# 2_1.net
KiCad netlist of a schematic drawn in Altium Designer
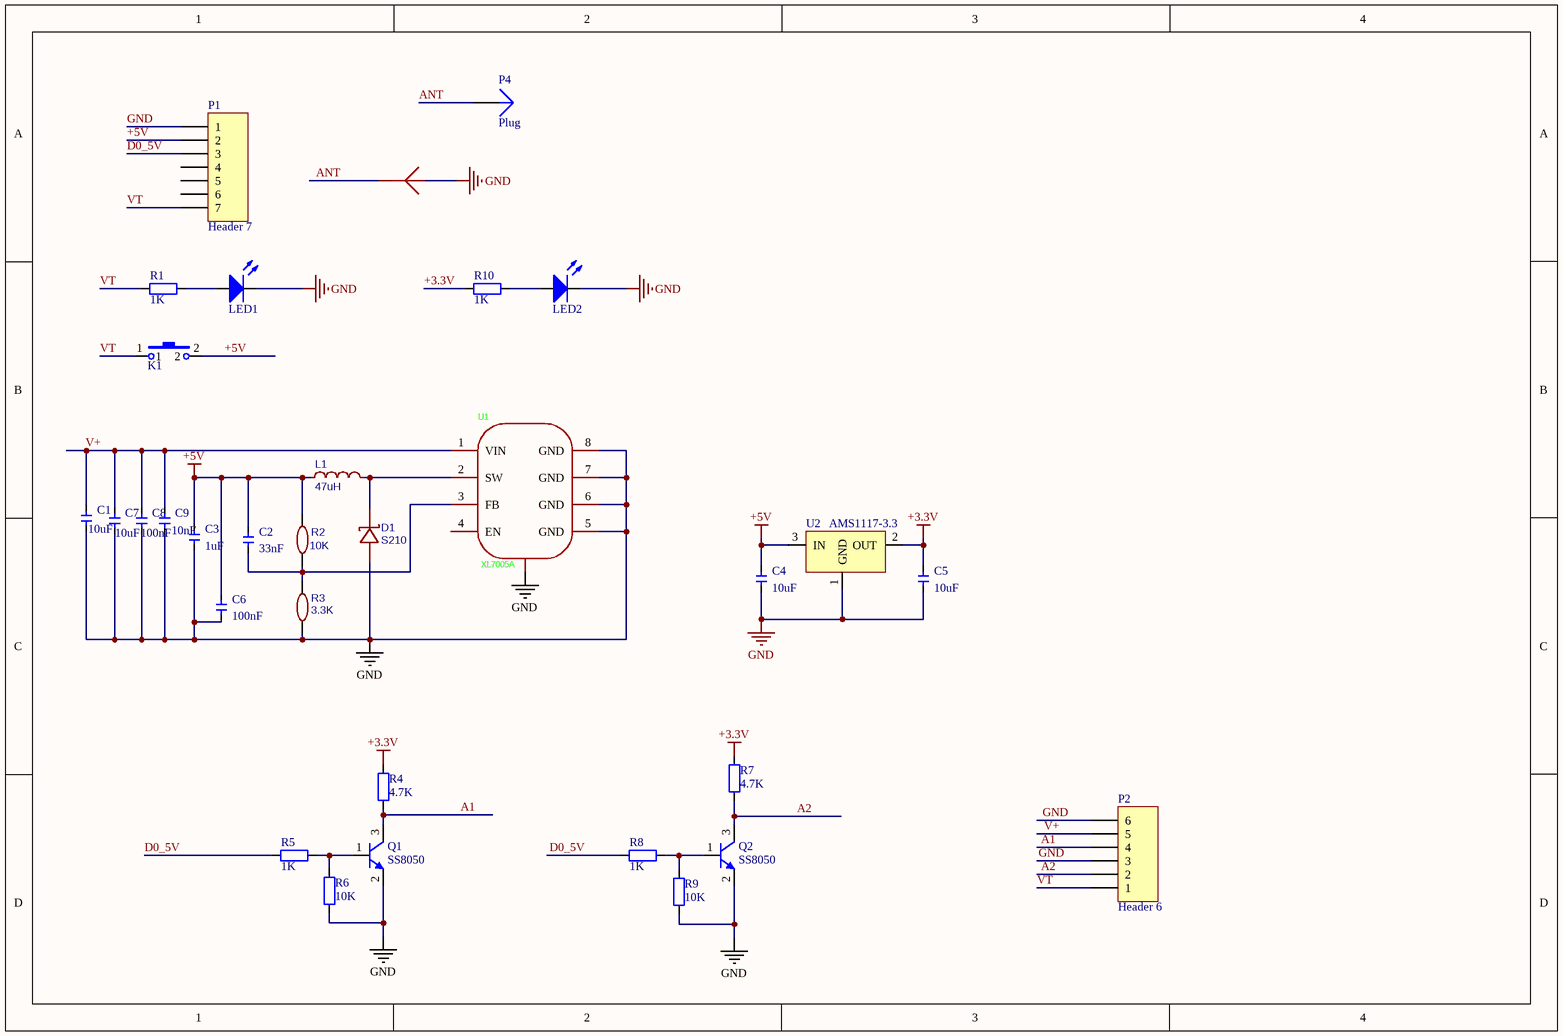
[diagram p0: 遥控2.1.SchDoc]

(export (version "E")
  (design (tool "Eeschema 10.0.6"))
  (components
    (comp (ref "C1")
      (value "10uF")
      (footprint "0805")
      (description "无极性电容")
      (fields (field (name "PUBLISHER") "Altium Limited"))
      (libsource (lib "Arrowy_Racing") (part "Cap"))
    )
    (comp (ref "C2")
      (value "33nF")
      (footprint "CAP-0603")
      (description "无极性电容")
      (fields (field (name "PUBLISHER") "Altium Limited"))
      (libsource (lib "Arrowy_Racing") (part "Cap"))
    )
    (comp (ref "C3")
      (value "1uF")
      (footprint "CAP-0603")
      (description "无极性电容")
      (fields (field (name "PUBLISHER") "Altium Limited"))
      (libsource (lib "Arrowy_Racing") (part "Cap"))
    )
    (comp (ref "C4")
      (value "10uF")
      (footprint "CAP-0603")
      (description "无极性电容")
      (fields (field (name "PUBLISHER") "Altium Limited"))
      (libsource (lib "Arrowy_Racing") (part "Cap"))
    )
    (comp (ref "C5")
      (value "10uF")
      (footprint "CAP-0603")
      (description "无极性电容")
      (fields (field (name "PUBLISHER") "Altium Limited"))
      (libsource (lib "Arrowy_Racing") (part "Cap"))
    )
    (comp (ref "C6")
      (value "100nF")
      (footprint "CAP-0603")
      (description "无极性电容")
      (fields (field (name "PUBLISHER") "Altium Limited"))
      (libsource (lib "Arrowy_Racing") (part "Cap"))
    )
    (comp (ref "C7")
      (value "10uF")
      (footprint "0805")
      (description "无极性电容")
      (fields (field (name "PUBLISHER") "Altium Limited"))
      (libsource (lib "Arrowy_Racing") (part "Cap"))
    )
    (comp (ref "C8")
      (value "100nF")
      (footprint "0805")
      (description "无极性电容")
      (fields (field (name "PUBLISHER") "Altium Limited"))
      (libsource (lib "Arrowy_Racing") (part "Cap"))
    )
    (comp (ref "C9")
      (value "10nF")
      (footprint "0805")
      (description "无极性电容")
      (fields (field (name "PUBLISHER") "Altium Limited"))
      (libsource (lib "Arrowy_Racing") (part "Cap"))
    )
    (comp (ref "D1")
      (value "S210")
      (footprint "SOD-123")
      (fields (field (name "MANUFACTURER PART") "B340A") (field (name "MANUFACTURER") "MDD"))
      (libsource (lib "altium-import") (part "root_3_B340A_"))
    )
    (comp (ref "K1")
      (value "SW-PB")
      (footprint "SW-SMD_L3.9-W3.0-P4.45")
      (description "微动开关")
      (fields (field (name "SUPPLITER PART") "C961737") (field (name "PUBLISHER") "Altium Limited"))
      (libsource (lib "Arrowy_Racing") (part "SW-PB"))
    )
    (comp (ref "L1")
      (value "47uH")
      (footprint "IND-SMD_L4.0-W4.0_FNR4012S")
      (fields (field (name "MANUFACTURER") "SXN") (field (name "MANUFACTURER PART") "SMDRI127-680MT"))
      (libsource (lib "altium-import") (part "root_0_68uH_"))
    )
    (comp (ref "L2")
      (value "400-1000mhz-chip(b&t-1503)")
      (footprint "ANT-SMD_L15.0-W3.0")
      (description "天线类型:贴片天线;中心频率:700MHz;带宽:600MHz;增益:2dBi;功率:4W;驻波比:2;")
      (fields
        (field (name "MANUFACTURER") "Ai-Thinker(安信可)")
        (field (name "MANUFACTURERPART") "400-1000MHz-chip(B&T-1503)")
      )
      (libsource (lib "altium-import") (part "root_3_400-1000mhz-chip(b&t-1503)_"))
    )
    (comp (ref "LED1")
      (value "LED")
      (footprint "LED_0805")
      (description "发光二极管")
      (fields (field (name "PUBLISHER") "Altium Limited"))
      (libsource (lib "Arrowy_Racing") (part "LED"))
    )
    (comp (ref "LED2")
      (value "LED")
      (footprint "LED_0805")
      (description "发光二极管")
      (fields (field (name "PUBLISHER") "Altium Limited"))
      (libsource (lib "Arrowy_Racing") (part "LED"))
    )
    (comp (ref "P1")
      (value "Header 7")
      (footprint "HDR1X7")
      (description "Header, 7-Pin")
      (fields (field (name "PUBLISHER") "Altium Limited"))
      (libsource (lib "Miscellaneous Connectors") (part "Header 7"))
    )
    (comp (ref "P2")
      (value "Header 6")
      (footprint "HDR1X6")
      (description "Header, 6-Pin")
      (fields (field (name "PUBLISHER") "Altium Limited"))
      (libsource (lib "Miscellaneous Connectors") (part "Header 6"))
    )
    (comp (ref "P4")
      (value "Plug")
      (footprint "HEADER_1")
      (description "安装孔")
      (fields (field (name "PUBLISHER") "Altium Limited"))
      (libsource (lib "Arrowy_Racing") (part "Plug"))
    )
    (comp (ref "Q1")
      (value "SS8050")
      (footprint "SOT-23")
      (description "NPN贴片三极管")
      (fields (field (name "PUBLISHER") "Altium Limited"))
      (libsource (lib "Arrowy_Racing") (part "SS8050"))
    )
    (comp (ref "Q2")
      (value "SS8050")
      (footprint "SOT-23")
      (description "NPN贴片三极管")
      (fields (field (name "PUBLISHER") "Altium Limited"))
      (libsource (lib "Arrowy_Racing") (part "SS8050"))
    )
    (comp (ref "R1")
      (value "1K")
      (footprint "0603 - duplicate1")
      (description "贴片电阻")
      (fields (field (name "PUBLISHER") "Altium Limited"))
      (libsource (lib "") (part "Res_1"))
    )
    (comp (ref "R2")
      (value "10K")
      (footprint "0603 - duplicate1")
      (fields (field (name "MANUFACTURER") "UniOhm") (field (name "MANUFACTURER PART") "0603WAF1001T5E"))
      (libsource (lib "altium-import") (part "root_1_1K_"))
    )
    (comp (ref "R3")
      (value "3.3K")
      (footprint "0603 - duplicate1")
      (fields (field (name "MANUFACTURER") "UniOhm") (field (name "MANUFACTURER PART") "0603WAF3001T5E"))
      (libsource (lib "altium-import") (part "root_3_3K_"))
    )
    (comp (ref "R4")
      (value "4.7K")
      (footprint "0603 - duplicate1")
      (description "贴片电阻")
      (fields (field (name "PUBLISHER") "Altium Limited"))
      (libsource (lib "") (part "Res_3"))
    )
    (comp (ref "R5")
      (value "1K")
      (footprint "0603 - duplicate1")
      (description "贴片电阻")
      (fields (field (name "PUBLISHER") "Altium Limited"))
      (libsource (lib "") (part "Res_2"))
    )
    (comp (ref "R6")
      (value "10K")
      (footprint "0603 - duplicate1")
      (description "贴片电阻")
      (fields (field (name "PUBLISHER") "Altium Limited"))
      (libsource (lib "Arrowy_Racing") (part "Res"))
    )
    (comp (ref "R7")
      (value "4.7K")
      (footprint "0603 - duplicate1")
      (description "贴片电阻")
      (fields (field (name "PUBLISHER") "Altium Limited"))
      (libsource (lib "") (part "Res_3"))
    )
    (comp (ref "R8")
      (value "1K")
      (footprint "0603 - duplicate1")
      (description "贴片电阻")
      (fields (field (name "PUBLISHER") "Altium Limited"))
      (libsource (lib "") (part "Res_2"))
    )
    (comp (ref "R9")
      (value "10K")
      (footprint "0603 - duplicate1")
      (description "贴片电阻")
      (fields (field (name "PUBLISHER") "Altium Limited"))
      (libsource (lib "Arrowy_Racing") (part "Res"))
    )
    (comp (ref "R10")
      (value "1K")
      (footprint "0603 - duplicate1")
      (description "贴片电阻")
      (fields (field (name "PUBLISHER") "Altium Limited"))
      (libsource (lib "") (part "Res_1"))
    )
    (comp (ref "U1")
      (value "XL7005A")
      (footprint "SOIC-8_L4.9-W3.9-P1.27-LS6.0-BL-EP3.1-1")
      (fields (field (name "MANUFACTURER") "XLSEMI(芯龙)"))
      (libsource (lib "altium-import") (part "root_0_XL7005A_"))
    )
    (comp (ref "U2")
      (value "AMS1117-3.3")
      (footprint "SOT89")
      (description "3.3V稳压芯片")
      (libsource (lib "Arrowy_Racing") (part "AMS1117"))
    )
  )
  (nets
    (net (code "1") (name "+3.3V") (class "Default")
      (node (ref "C5") (pin "2") (pinfunction "2_2") (pintype "passive"))
      (node (ref "R10") (pin "2") (pinfunction "2_2") (pintype "passive"))
      (node (ref "R4") (pin "1") (pinfunction "1_1") (pintype "passive"))
      (node (ref "R7") (pin "1") (pinfunction "1_1") (pintype "passive"))
      (node (ref "U2") (pin "2") (pinfunction "OUT_2") (pintype "passive"))
    )
    (net (code "2") (name "+5V") (class "Default")
      (node (ref "C2") (pin "2") (pinfunction "2_2") (pintype "passive"))
      (node (ref "C3") (pin "2") (pinfunction "2_2") (pintype "passive"))
      (node (ref "C4") (pin "2") (pinfunction "2_2") (pintype "passive"))
      (node (ref "C6") (pin "2") (pinfunction "2_2") (pintype "passive"))
      (node (ref "K1") (pin "2") (pinfunction "2_2") (pintype "passive"))
      (node (ref "L1") (pin "1") (pinfunction "1_1") (pintype "passive"))
      (node (ref "P1") (pin "2") (pinfunction "2_2") (pintype "passive"))
      (node (ref "R2") (pin "2") (pinfunction "2_2") (pintype "passive"))
      (node (ref "U2") (pin "3") (pinfunction "IN_3") (pintype "passive"))
    )
    (net (code "3") (name "/A1") (class "Default")
      (node (ref "P2") (pin "4") (pinfunction "4_4") (pintype "passive"))
      (node (ref "Q1") (pin "3") (pinfunction "C_3") (pintype "passive"))
      (node (ref "R4") (pin "2") (pinfunction "2_2") (pintype "passive"))
    )
    (net (code "4") (name "/A2") (class "Default")
      (node (ref "P2") (pin "2") (pinfunction "2_2") (pintype "passive"))
      (node (ref "Q2") (pin "3") (pinfunction "C_3") (pintype "passive"))
      (node (ref "R7") (pin "2") (pinfunction "2_2") (pintype "passive"))
    )
    (net (code "5") (name "/ANT") (class "Default")
      (node (ref "L2") (pin "1") (pinfunction "ANT_1") (pintype "passive"))
      (node (ref "P4") (pin "1") (pinfunction "1_1") (pintype "passive"))
    )
    (net (code "6") (name "/D0_5V") (class "Default")
      (node (ref "P1") (pin "3") (pinfunction "3_3") (pintype "passive"))
      (node (ref "R5") (pin "1") (pinfunction "1_1") (pintype "passive"))
      (node (ref "R8") (pin "1") (pinfunction "1_1") (pintype "passive"))
    )
    (net (code "7") (name "/V+") (class "Default")
      (node (ref "C1") (pin "2") (pinfunction "2_2") (pintype "passive"))
      (node (ref "C7") (pin "2") (pinfunction "2_2") (pintype "passive"))
      (node (ref "C8") (pin "2") (pinfunction "2_2") (pintype "passive"))
      (node (ref "C9") (pin "2") (pinfunction "2_2") (pintype "passive"))
      (node (ref "P2") (pin "5") (pinfunction "5_5") (pintype "passive"))
      (node (ref "U1") (pin "1") (pinfunction "VIN_1") (pintype "passive"))
    )
    (net (code "8") (name "/VT") (class "Default")
      (node (ref "K1") (pin "1") (pinfunction "1_1") (pintype "passive"))
      (node (ref "P1") (pin "7") (pinfunction "7_7") (pintype "passive"))
      (node (ref "P2") (pin "1") (pinfunction "1_1") (pintype "passive"))
      (node (ref "R1") (pin "2") (pinfunction "2_2") (pintype "passive"))
    )
    (net (code "9") (name "GND") (class "Default")
      (node (ref "C1") (pin "1") (pinfunction "1_1") (pintype "passive"))
      (node (ref "C3") (pin "1") (pinfunction "1_1") (pintype "passive"))
      (node (ref "C4") (pin "1") (pinfunction "1_1") (pintype "passive"))
      (node (ref "C5") (pin "1") (pinfunction "1_1") (pintype "passive"))
      (node (ref "C6") (pin "1") (pinfunction "1_1") (pintype "passive"))
      (node (ref "C7") (pin "1") (pinfunction "1_1") (pintype "passive"))
      (node (ref "C8") (pin "1") (pinfunction "1_1") (pintype "passive"))
      (node (ref "C9") (pin "1") (pinfunction "1_1") (pintype "passive"))
      (node (ref "D1") (pin "2") (pinfunction "A_2") (pintype "passive"))
      (node (ref "L2") (pin "2") (pinfunction "2_2") (pintype "passive"))
      (node (ref "LED1") (pin "2") (pinfunction "K_2") (pintype "passive"))
      (node (ref "LED2") (pin "2") (pinfunction "K_2") (pintype "passive"))
      (node (ref "P1") (pin "1") (pinfunction "1_1") (pintype "passive"))
      (node (ref "P2") (pin "3") (pinfunction "3_3") (pintype "passive"))
      (node (ref "P2") (pin "6") (pinfunction "6_6") (pintype "passive"))
      (node (ref "Q1") (pin "2") (pinfunction "E_2") (pintype "passive"))
      (node (ref "Q2") (pin "2") (pinfunction "E_2") (pintype "passive"))
      (node (ref "R3") (pin "2") (pinfunction "2_2") (pintype "passive"))
      (node (ref "R6") (pin "1") (pinfunction "1_1") (pintype "passive"))
      (node (ref "R9") (pin "1") (pinfunction "1_1") (pintype "passive"))
      (node (ref "U1") (pin "5") (pinfunction "GND_5") (pintype "passive"))
      (node (ref "U1") (pin "6") (pinfunction "GND_6") (pintype "passive"))
      (node (ref "U1") (pin "7") (pinfunction "GND_7") (pintype "passive"))
      (node (ref "U1") (pin "8") (pinfunction "GND_8") (pintype "passive"))
      (node (ref "U1") (pin "9") (pinfunction "9_9") (pintype "passive"))
      (node (ref "U2") (pin "1") (pinfunction "GND_1") (pintype "passive"))
    )
    (net (code "10") (name "Net-(D1-K)") (class "Default")
      (node (ref "D1") (pin "1") (pinfunction "K_1") (pintype "passive"))
      (node (ref "L1") (pin "2") (pinfunction "2_2") (pintype "passive"))
      (node (ref "U1") (pin "2") (pinfunction "SW_2") (pintype "passive"))
    )
    (net (code "11") (name "Net-(LED1-A)") (class "Default")
      (node (ref "LED1") (pin "1") (pinfunction "A_1") (pintype "passive"))
      (node (ref "R1") (pin "1") (pinfunction "1_1") (pintype "passive"))
    )
    (net (code "12") (name "Net-(LED2-A)") (class "Default")
      (node (ref "LED2") (pin "1") (pinfunction "A_1") (pintype "passive"))
      (node (ref "R10") (pin "1") (pinfunction "1_1") (pintype "passive"))
    )
    (net (code "13") (name "Net-(Q1-B)") (class "Default")
      (node (ref "Q1") (pin "1") (pinfunction "B_1") (pintype "passive"))
      (node (ref "R5") (pin "2") (pinfunction "2_2") (pintype "passive"))
      (node (ref "R6") (pin "2") (pinfunction "2_2") (pintype "passive"))
    )
    (net (code "14") (name "Net-(Q2-B)") (class "Default")
      (node (ref "Q2") (pin "1") (pinfunction "B_1") (pintype "passive"))
      (node (ref "R8") (pin "2") (pinfunction "2_2") (pintype "passive"))
      (node (ref "R9") (pin "2") (pinfunction "2_2") (pintype "passive"))
    )
    (net (code "15") (name "Net-(U1-FB)") (class "Default")
      (node (ref "C2") (pin "1") (pinfunction "1_1") (pintype "passive"))
      (node (ref "R2") (pin "1") (pinfunction "1_1") (pintype "passive"))
      (node (ref "R3") (pin "1") (pinfunction "1_1") (pintype "passive"))
      (node (ref "U1") (pin "3") (pinfunction "FB_3") (pintype "passive"))
    )
    (net (code "16") (name "unconnected-(P1-Pad4)") (class "Default")
      (node (ref "P1") (pin "4") (pinfunction "4_4") (pintype "passive"))
    )
    (net (code "17") (name "unconnected-(P1-Pad5)") (class "Default")
      (node (ref "P1") (pin "5") (pinfunction "5_5") (pintype "passive"))
    )
    (net (code "18") (name "unconnected-(P1-Pad6)") (class "Default")
      (node (ref "P1") (pin "6") (pinfunction "6_6") (pintype "passive"))
    )
    (net (code "19") (name "unconnected-(U1-EN-Pad4)") (class "Default")
      (node (ref "U1") (pin "4") (pinfunction "EN_4") (pintype "passive"))
    )
  )
)
